# Sheet1.net
KiCad netlist of a schematic drawn in Altium Designer
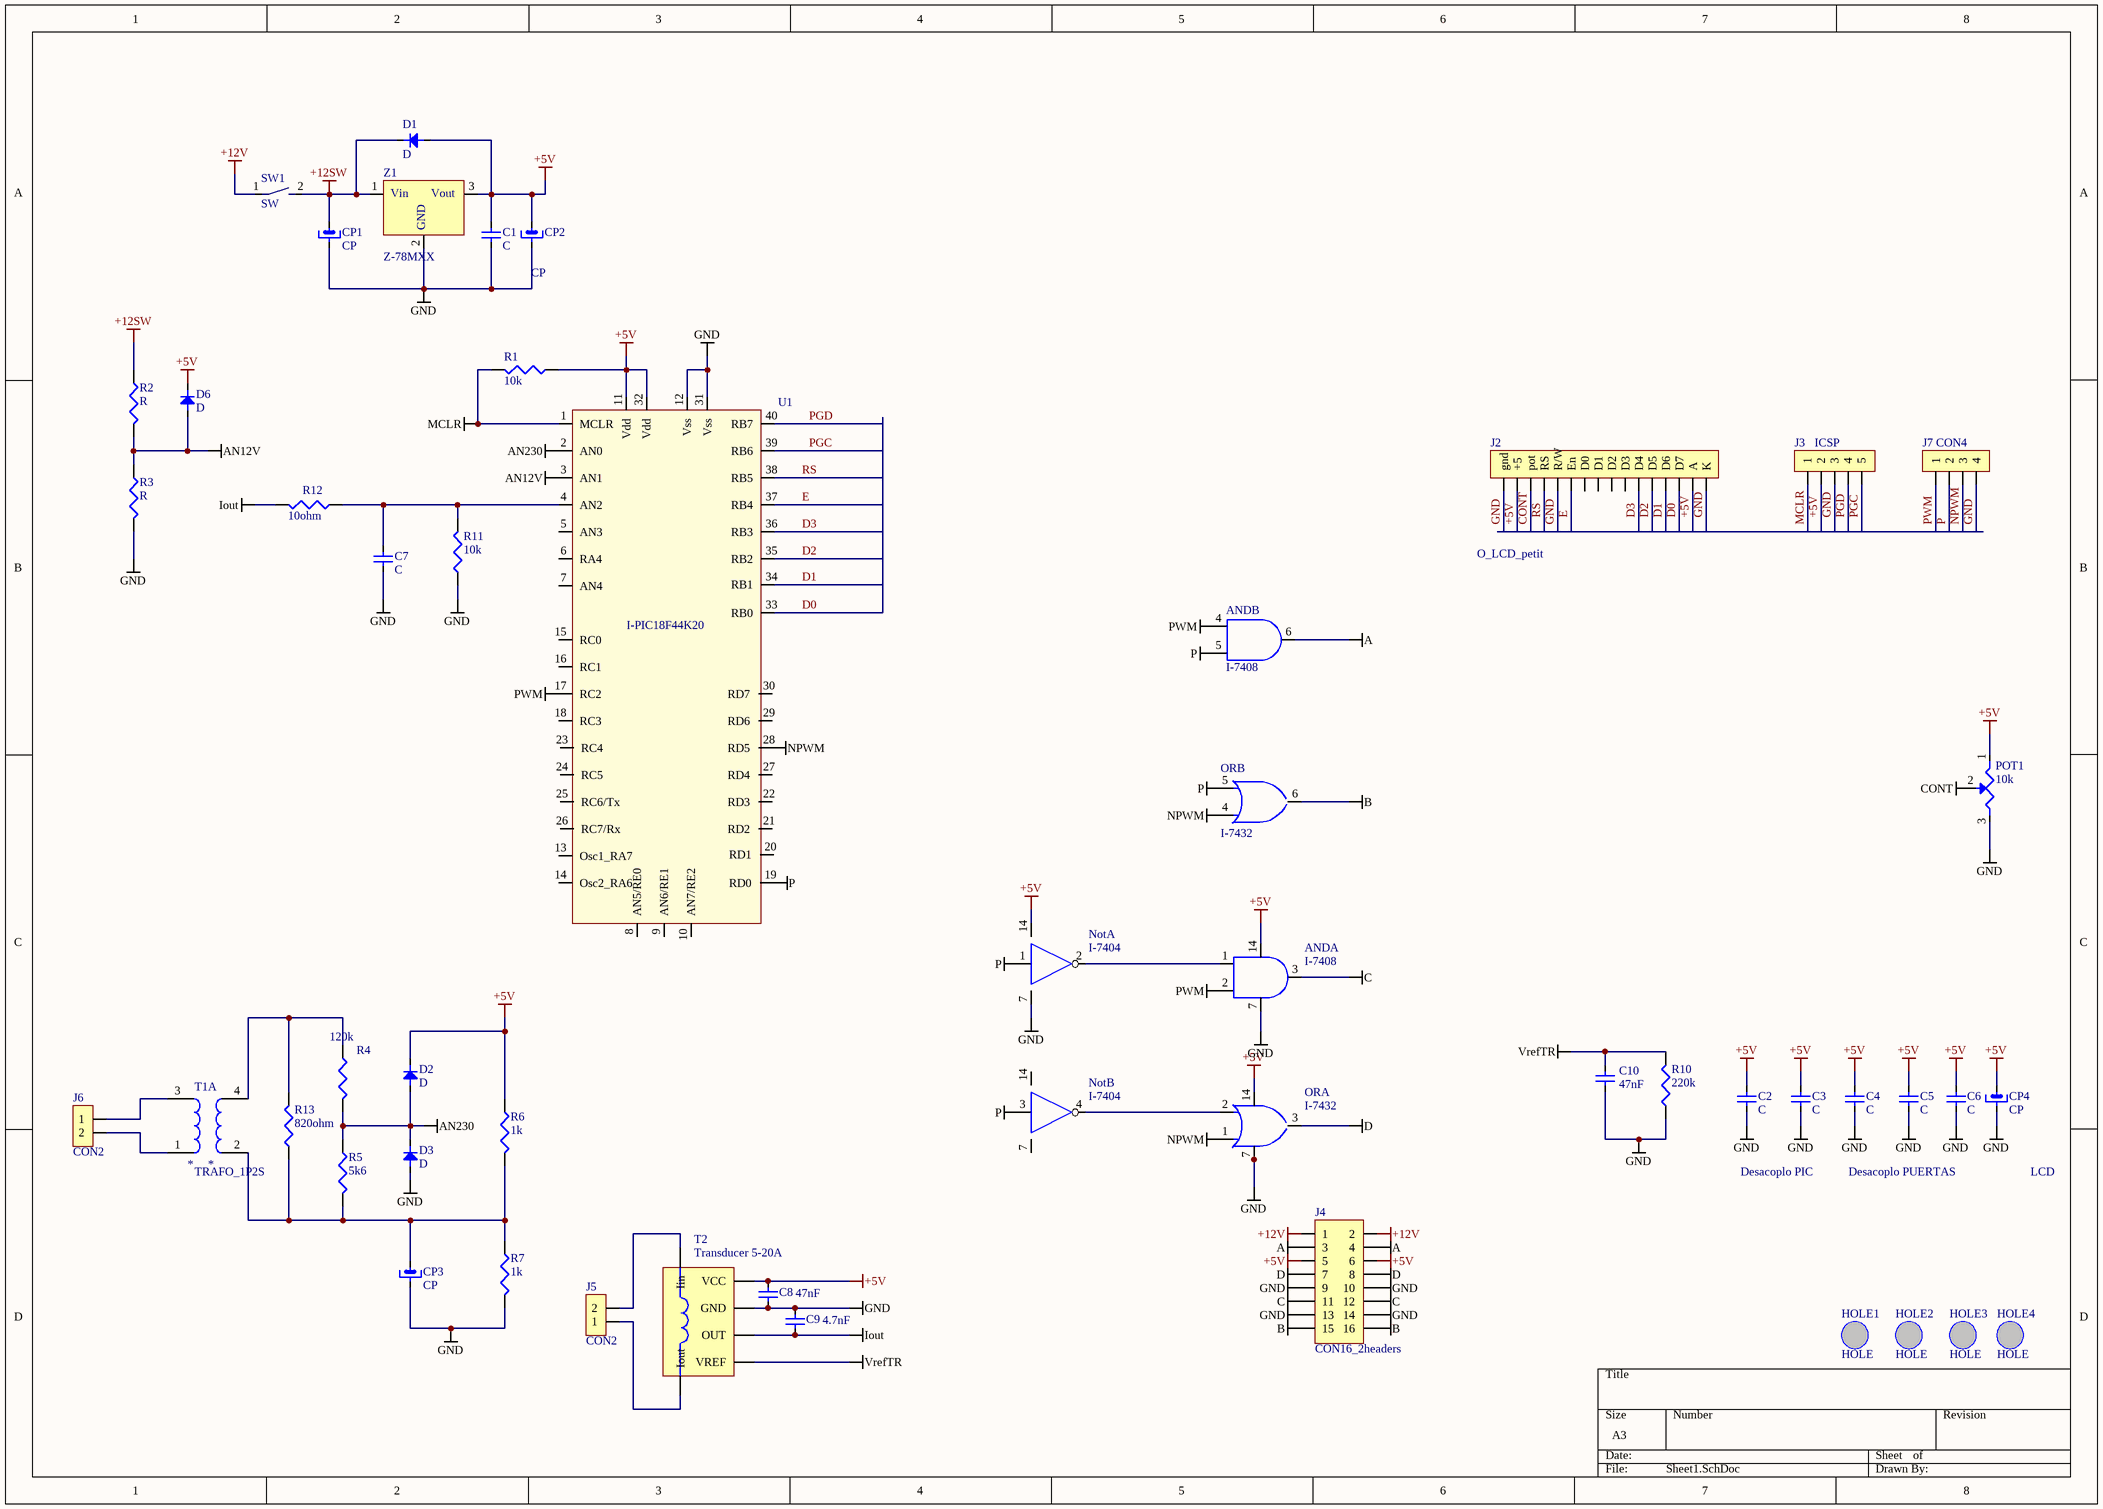
[diagram p0: Sheet1.SchDoc]

(export (version "E")
  (design (tool "Eeschema 10.0.6"))
  (components
    (comp (ref "AND")
      (value "I-7408")
      (footprint "DIP14")
      (description "Cuadruple 2 input Schmitt trigger NAND gate")
      (libsource (lib "Symbols_WOME") (part "I-7408"))
    )
    (comp (ref "C1")
      (value "C")
      (footprint "C2_200mils")
      (description ";C?;C1206;C2_25x7i5;C4_15x5 ;C0805 ;Condensador baja potencia ;2")
      (libsource (lib "Symbols_WOME") (part "C"))
    )
    (comp (ref "C2")
      (value "C")
      (footprint "C2_200mils")
      (description ";C?;C1206;C2_25x7i5;C4_15x5 ;C0805 ;Condensador baja potencia ;2")
      (libsource (lib "Symbols_WOME") (part "C"))
    )
    (comp (ref "C3")
      (value "C")
      (footprint "C2_200mils")
      (description ";C?;C1206;C2_25x7i5;C4_15x5 ;C0805 ;Condensador baja potencia ;2")
      (libsource (lib "Symbols_WOME") (part "C"))
    )
    (comp (ref "C4")
      (value "C")
      (footprint "C2_200mils")
      (description ";C?;C1206;C2_25x7i5;C4_15x5 ;C0805 ;Condensador baja potencia ;2")
      (libsource (lib "Symbols_WOME") (part "C"))
    )
    (comp (ref "C5")
      (value "C")
      (footprint "C2_200mils")
      (description ";C?;C1206;C2_25x7i5;C4_15x5 ;C0805 ;Condensador baja potencia ;2")
      (libsource (lib "Symbols_WOME") (part "C"))
    )
    (comp (ref "C6")
      (value "C")
      (footprint "C2_200mils")
      (description ";C?;C1206;C2_25x7i5;C4_15x5 ;C0805 ;Condensador baja potencia ;2")
      (libsource (lib "Symbols_WOME") (part "C"))
    )
    (comp (ref "C7")
      (value "C")
      (footprint "C2_200mils")
      (description ";C?;C1206;C2_25x7i5;C4_15x5 ;C0805 ;Condensador baja potencia ;2")
      (libsource (lib "Symbols_WOME") (part "C"))
    )
    (comp (ref "C8")
      (value "47nF")
      (footprint "C2_200mils")
      (description ";C?;C1206;C2_25x7i5;C4_15x5 ;C0805 ;Condensador baja potencia ;2")
      (libsource (lib "Symbols_WOME") (part "C"))
    )
    (comp (ref "C9")
      (value "4.7nF")
      (footprint "C2_200mils")
      (description ";C?;C1206;C2_25x7i5;C4_15x5 ;C0805 ;Condensador baja potencia ;2")
      (libsource (lib "Symbols_WOME") (part "C"))
    )
    (comp (ref "C10")
      (value "47nF")
      (footprint "C2_200mils")
      (description ";C?;C1206;C2_25x7i5;C4_15x5 ;C0805 ;Condensador baja potencia ;2")
      (libsource (lib "Symbols_WOME") (part "C"))
    )
    (comp (ref "CP1")
      (value "CP")
      (footprint "CP1_D5i5")
      (description ";CP? ;CP1_D5i5 ;CP2_D10i5 ;CP2_D13 ;CP4_D36 ;Condensador polarizado ;3")
      (libsource (lib "Symbols_WOME") (part "CP"))
    )
    (comp (ref "CP2")
      (value "CP")
      (footprint "CP1_D5i5")
      (description ";CP? ;CP1_D5i5 ;CP2_D10i5 ;CP2_D13 ;CP4_D36 ;Condensador polarizado ;3")
      (libsource (lib "Symbols_WOME") (part "CP"))
    )
    (comp (ref "CP3")
      (value "CP")
      (footprint "CP1_D5i5")
      (description ";CP? ;CP1_D5i5 ;CP2_D10i5 ;CP2_D13 ;CP4_D36 ;Condensador polarizado ;3")
      (libsource (lib "Symbols_WOME") (part "CP"))
    )
    (comp (ref "CP4")
      (value "CP")
      (footprint "CP1_D5i5")
      (description ";CP? ;CP1_D5i5 ;CP2_D10i5 ;CP2_D13 ;CP4_D36 ;Condensador polarizado ;3")
      (libsource (lib "Symbols_WOME") (part "CP"))
    )
    (comp (ref "D1")
      (value "D")
      (footprint "DO35")
      (description ";D? ;SOD80;DO41 ;melf ;minimelf ; Diodo de señal o baja potencia ;8")
      (libsource (lib "Symbols_WOME") (part "D"))
    )
    (comp (ref "D2")
      (value "D")
      (footprint "DO35")
      (description ";D? ;SOD80;DO41 ;melf ;minimelf ; Diodo de señal o baja potencia ;8")
      (libsource (lib "Symbols_WOME") (part "D"))
    )
    (comp (ref "D3")
      (value "D")
      (footprint "DO35")
      (description ";D? ;SOD80;DO41 ;melf ;minimelf ; Diodo de señal o baja potencia ;8")
      (libsource (lib "Symbols_WOME") (part "D"))
    )
    (comp (ref "D6")
      (value "D")
      (footprint "DO35")
      (description ";D? ;SOD80;DO41 ;melf ;minimelf ; Diodo de señal o baja potencia ;8")
      (libsource (lib "Symbols_WOME") (part "D"))
    )
    (comp (ref "HOLE1")
      (value "HOLE")
      (footprint "HOLE3_D6")
      (description ";HOLE? ;HOLE3_D6 ; ; ;Agujero ;20")
      (libsource (lib "Symbols_WOME") (part "HOLE"))
    )
    (comp (ref "HOLE2")
      (value "HOLE")
      (footprint "HOLE3_D6")
      (description ";HOLE? ;HOLE3_D6 ; ; ;Agujero ;20")
      (libsource (lib "Symbols_WOME") (part "HOLE"))
    )
    (comp (ref "HOLE3")
      (value "HOLE")
      (footprint "HOLE3_D6")
      (description ";HOLE? ;HOLE3_D6 ; ; ;Agujero ;20")
      (libsource (lib "Symbols_WOME") (part "HOLE"))
    )
    (comp (ref "HOLE4")
      (value "HOLE")
      (footprint "HOLE3_D6")
      (description ";HOLE? ;HOLE3_D6 ; ; ;Agujero ;20")
      (libsource (lib "Symbols_WOME") (part "HOLE"))
    )
    (comp (ref "J2")
      (value "O_LCD_petit")
      (footprint "O_LCDpetit")
      (libsource (lib "Symbols_WOME") (part "O_LCD_petit"))
    )
    (comp (ref "J3")
      (value "ICSP")
      (footprint "CON5_2I54V")
      (description ";J? ;CON5 ;CON5_2i54VE_JST_B2PVH ;CON5_7I62_STL960-HG-3 ;CON5_2I54V;Conector de 5 pins simples ;17")
      (libsource (lib "Symbols_WOME") (part "CON5"))
    )
    (comp (ref "J4")
      (value "CON16_2headers")
      (footprint "CON16-2headers")
      (description ";J? ;CON5 ;CON5_2i54VE_JST_B2PVH ;CON5_7I62_STL960-HG-3 ;CON5_2I54V;Conector de 5 pins simples ;17")
      (libsource (lib "Symbols_WOME") (part "CON16_2headers"))
    )
    (comp (ref "J5")
      (value "CON2")
      (footprint "CON2_5I08V_CP")
      (libsource (lib "Symbols_WOME") (part "CON2"))
    )
    (comp (ref "J6") (value "CON2") (footprint "CON2_5I08V_CP") (libsource (lib "") (part "CON2_1")))
    (comp (ref "J7") (value "CON4") (footprint "CON4_2I54V") (libsource (lib "Symbols_WOME") (part "CON4")))
    (comp (ref "Not")
      (value "I-7404")
      (footprint "DIP14")
      (description ";U? ;DIP-14 ; ; ; ;6xInversor trigger smith ;18")
      (libsource (lib "Symbols_WOME") (part "I-7404"))
    )
    (comp (ref "OR")
      (value "I-7432")
      (footprint "DIP14")
      (description ";U? ;SOIC14 ; ; ; ; NOR x 4 ;18")
      (libsource (lib "Symbols_WOME") (part "I-7432"))
    )
    (comp (ref "POT1")
      (value "10k")
      (footprint "PT15V")
      (description ";PT? ;PTV1 ;PT15V ;PTH ;PTH1 ;Potenciometro generico ;1")
      (libsource (lib "Symbols_WOME") (part "POT1"))
    )
    (comp (ref "R1")
      (value "10k")
      (footprint "R1/4")
      (description ";R? ;R1206 ;R1/4 ;R1/2 ;R0805 ;Resistencia baja potencia (<=1/2W) ;1")
      (libsource (lib "Symbols_WOME") (part "R"))
    )
    (comp (ref "R2")
      (value "R")
      (footprint "R1/4")
      (description ";R? ;R1206 ;R1/4 ;R1/2 ;R0805 ;Resistencia baja potencia (<=1/2W) ;1")
      (libsource (lib "Symbols_WOME") (part "R"))
    )
    (comp (ref "R3")
      (value "R")
      (footprint "R1/4")
      (description ";R? ;R1206 ;R1/4 ;R1/2 ;R0805 ;Resistencia baja potencia (<=1/2W) ;1")
      (libsource (lib "Symbols_WOME") (part "R"))
    )
    (comp (ref "R4")
      (value "120k")
      (footprint "R1/4")
      (description ";R? ;R1206 ;R1/4 ;R1/2 ;R0805 ;Resistencia baja potencia (<=1/2W) ;1")
      (libsource (lib "Symbols_WOME") (part "R"))
    )
    (comp (ref "R5")
      (value "5k6")
      (footprint "R1/4")
      (description ";R? ;R1206 ;R1/4 ;R1/2 ;R0805 ;Resistencia baja potencia (<=1/2W) ;1")
      (libsource (lib "Symbols_WOME") (part "R"))
    )
    (comp (ref "R6")
      (value "1k")
      (footprint "R1/4")
      (description ";R? ;R1206 ;R1/4 ;R1/2 ;R0805 ;Resistencia baja potencia (<=1/2W) ;1")
      (libsource (lib "Symbols_WOME") (part "R"))
    )
    (comp (ref "R7")
      (value "1k")
      (footprint "R1/4")
      (description ";R? ;R1206 ;R1/4 ;R1/2 ;R0805 ;Resistencia baja potencia (<=1/2W) ;1")
      (libsource (lib "Symbols_WOME") (part "R"))
    )
    (comp (ref "R10")
      (value "220k")
      (footprint "R1/4")
      (description ";R? ;R1206 ;R1/4 ;R1/2 ;R0805 ;Resistencia baja potencia (<=1/2W) ;1")
      (libsource (lib "Symbols_WOME") (part "R"))
    )
    (comp (ref "R11")
      (value "10k")
      (footprint "R1/4")
      (description ";R? ;R1206 ;R1/4 ;R1/2 ;R0805 ;Resistencia baja potencia (<=1/2W) ;1")
      (libsource (lib "Symbols_WOME") (part "R"))
    )
    (comp (ref "R12")
      (value "10ohm")
      (footprint "R1/4")
      (description ";R? ;R1206 ;R1/4 ;R1/2 ;R0805 ;Resistencia baja potencia (<=1/2W) ;1")
      (libsource (lib "Symbols_WOME") (part "R"))
    )
    (comp (ref "R13")
      (value "820ohm")
      (footprint "R1/4")
      (description ";R? ;R1206 ;R1/4 ;R1/2 ;R0805 ;Resistencia baja potencia (<=1/2W) ;1")
      (libsource (lib "Symbols_WOME") (part "R"))
    )
    (comp (ref "SW1")
      (value "SW")
      (footprint "SW1SPDT")
      (description ";SW? ; ; ; ; ;Switch ;")
      (libsource (lib "Symbols_WOME") (part "SW"))
    )
    (comp (ref "T1")
      (value "TRAFO_1P2S")
      (footprint "TR_0.35/1/12")
      (description ";T? ;TR-TOR1P-2S ; ; ; ;Transformador con 2 secundarios \"2part\" ;6")
      (libsource (lib "Symbols_WOME") (part "TRAFO_1P2S"))
    )
    (comp (ref "T2")
      (value "Transducer 5-20A")
      (footprint "HXS 20-NP")
      (libsource (lib "Symbols_WOME") (part "Transducer 5-20A"))
    )
    (comp (ref "U1")
      (value "I-PIC18F44K20")
      (footprint "DIP40")
      (libsource (lib "Symbols_WOME") (part "I-PIC18F44K20"))
    )
    (comp (ref "Z1")
      (value "Z-78MXX")
      (footprint "TO220GDS_pla")
      (description ";Z? ;TO220 ;SOT233 ;TO220H_2COM ; ;Regulador Lineal ;11")
      (libsource (lib "Symbols_WOME") (part "Z-78MXX"))
    )
  )
  (nets
    (net (code "1") (name "+5V") (class "Default")
      (node (ref "AND") (pin "14") (pinfunction "VCC_14") (pintype "passive"))
      (node (ref "C1") (pin "1") (pinfunction "1_1") (pintype "passive"))
      (node (ref "C2") (pin "1") (pinfunction "1_1") (pintype "passive"))
      (node (ref "C3") (pin "1") (pinfunction "1_1") (pintype "passive"))
      (node (ref "C4") (pin "1") (pinfunction "1_1") (pintype "passive"))
      (node (ref "C5") (pin "1") (pinfunction "1_1") (pintype "passive"))
      (node (ref "C6") (pin "1") (pinfunction "1_1") (pintype "passive"))
      (node (ref "C8") (pin "1") (pinfunction "1_1") (pintype "passive"))
      (node (ref "CP2") (pin "1") (pinfunction "1_1") (pintype "passive"))
      (node (ref "CP4") (pin "1") (pinfunction "1_1") (pintype "passive"))
      (node (ref "D1") (pin "1") (pinfunction "1_1") (pintype "passive"))
      (node (ref "D2") (pin "2") (pinfunction "2_2") (pintype "passive"))
      (node (ref "D6") (pin "2") (pinfunction "2_2") (pintype "passive"))
      (node (ref "J2") (pin "15") (pinfunction "A_15") (pintype "passive"))
      (node (ref "J2") (pin "2") (pinfunction "+5_2") (pintype "passive"))
      (node (ref "J3") (pin "2") (pinfunction "2_2") (pintype "passive"))
      (node (ref "J4") (pin "5") (pinfunction "5_5") (pintype "passive"))
      (node (ref "J4") (pin "6") (pinfunction "6_6") (pintype "passive"))
      (node (ref "Not") (pin "14") (pinfunction "VCC_14") (pintype "power_in"))
      (node (ref "OR") (pin "14") (pintype "passive"))
      (node (ref "POT1") (pin "1") (pinfunction "1_1") (pintype "passive"))
      (node (ref "R1") (pin "1") (pinfunction "1_1") (pintype "passive"))
      (node (ref "R6") (pin "1") (pinfunction "1_1") (pintype "passive"))
      (node (ref "T2") (pin "9") (pinfunction "VCC_9") (pintype "passive"))
      (node (ref "U1") (pin "11") (pinfunction "Vdd_11") (pintype "passive"))
      (node (ref "U1") (pin "32") (pinfunction "Vdd_32") (pintype "passive"))
      (node (ref "Z1") (pin "3") (pinfunction "3_3") (pintype "passive"))
    )
    (net (code "2") (name "+12SW") (class "Default")
      (node (ref "CP1") (pin "1") (pinfunction "1_1") (pintype "passive"))
      (node (ref "D1") (pin "2") (pinfunction "2_2") (pintype "passive"))
      (node (ref "R2") (pin "1") (pinfunction "1_1") (pintype "passive"))
      (node (ref "SW1") (pin "2") (pinfunction "2_2") (pintype "passive"))
      (node (ref "Z1") (pin "1") (pinfunction "1_1") (pintype "passive"))
    )
    (net (code "3") (name "+12V") (class "Default")
      (node (ref "J4") (pin "1") (pinfunction "1_1") (pintype "passive"))
      (node (ref "J4") (pin "2") (pinfunction "2_2") (pintype "passive"))
      (node (ref "SW1") (pin "1") (pinfunction "1_1") (pintype "passive"))
    )
    (net (code "4") (name "/D0") (class "Default")
      (node (ref "J2") (pin "14") (pinfunction "D7_14") (pintype "passive"))
      (node (ref "U1") (pin "33") (pinfunction "RB0_33") (pintype "passive"))
    )
    (net (code "5") (name "/D1") (class "Default")
      (node (ref "J2") (pin "13") (pinfunction "D6_13") (pintype "passive"))
      (node (ref "U1") (pin "34") (pinfunction "RB1_34") (pintype "passive"))
    )
    (net (code "6") (name "/D2") (class "Default")
      (node (ref "J2") (pin "12") (pinfunction "D5_12") (pintype "passive"))
      (node (ref "U1") (pin "35") (pinfunction "RB2_35") (pintype "passive"))
    )
    (net (code "7") (name "/D3") (class "Default")
      (node (ref "J2") (pin "11") (pinfunction "D4_11") (pintype "passive"))
      (node (ref "U1") (pin "36") (pinfunction "RB3_36") (pintype "passive"))
    )
    (net (code "8") (name "/E") (class "Default")
      (node (ref "J2") (pin "6") (pinfunction "En_6") (pintype "passive"))
      (node (ref "U1") (pin "37") (pinfunction "RB4_37") (pintype "passive"))
    )
    (net (code "9") (name "/PGC") (class "Default")
      (node (ref "J3") (pin "5") (pinfunction "5_5") (pintype "passive"))
      (node (ref "U1") (pin "39") (pinfunction "RB6_39") (pintype "passive"))
    )
    (net (code "10") (name "/PGD") (class "Default")
      (node (ref "J3") (pin "4") (pinfunction "4_4") (pintype "passive"))
      (node (ref "U1") (pin "40") (pinfunction "RB7_40") (pintype "passive"))
    )
    (net (code "11") (name "/RS") (class "Default")
      (node (ref "J2") (pin "4") (pinfunction "RS_4") (pintype "passive"))
      (node (ref "U1") (pin "38") (pinfunction "RB5_38") (pintype "passive"))
    )
    (net (code "12") (name "A") (class "Default")
      (node (ref "AND") (pin "6") (pinfunction "BO_6") (pintype "passive"))
      (node (ref "J4") (pin "3") (pinfunction "3_3") (pintype "passive"))
      (node (ref "J4") (pin "4") (pinfunction "4_4") (pintype "passive"))
    )
    (net (code "13") (name "AN12V") (class "Default")
      (node (ref "D6") (pin "1") (pinfunction "1_1") (pintype "passive"))
      (node (ref "R2") (pin "2") (pinfunction "2_2") (pintype "passive"))
      (node (ref "R3") (pin "1") (pinfunction "1_1") (pintype "passive"))
      (node (ref "U1") (pin "3") (pinfunction "AN1_3") (pintype "passive"))
    )
    (net (code "14") (name "AN230") (class "Default")
      (node (ref "D2") (pin "1") (pinfunction "1_1") (pintype "passive"))
      (node (ref "D3") (pin "2") (pinfunction "2_2") (pintype "passive"))
      (node (ref "R4") (pin "2") (pinfunction "2_2") (pintype "passive"))
      (node (ref "R5") (pin "1") (pinfunction "1_1") (pintype "passive"))
      (node (ref "U1") (pin "2") (pinfunction "AN0_2") (pintype "passive"))
    )
    (net (code "15") (name "B") (class "Default")
      (node (ref "J4") (pin "15") (pinfunction "15_15") (pintype "passive"))
      (node (ref "J4") (pin "16") (pinfunction "16_16") (pintype "passive"))
      (node (ref "OR") (pin "6") (pintype "passive"))
    )
    (net (code "16") (name "C") (class "Default")
      (node (ref "AND") (pin "3") (pinfunction "AO_3") (pintype "passive"))
      (node (ref "J4") (pin "11") (pinfunction "11_11") (pintype "passive"))
      (node (ref "J4") (pin "12") (pinfunction "12_12") (pintype "passive"))
    )
    (net (code "17") (name "CONT") (class "Default")
      (node (ref "J2") (pin "3") (pinfunction "pot_3") (pintype "passive"))
      (node (ref "POT1") (pin "2") (pinfunction "2_2") (pintype "passive"))
    )
    (net (code "18") (name "D") (class "Default")
      (node (ref "J4") (pin "7") (pinfunction "7_7") (pintype "passive"))
      (node (ref "J4") (pin "8") (pinfunction "8_8") (pintype "passive"))
      (node (ref "OR") (pin "3") (pintype "passive"))
    )
    (net (code "19") (name "GND") (class "Default")
      (node (ref "AND") (pin "7") (pinfunction "GND_7") (pintype "passive"))
      (node (ref "C1") (pin "2") (pinfunction "2_2") (pintype "passive"))
      (node (ref "C10") (pin "2") (pinfunction "2_2") (pintype "passive"))
      (node (ref "C2") (pin "2") (pinfunction "2_2") (pintype "passive"))
      (node (ref "C3") (pin "2") (pinfunction "2_2") (pintype "passive"))
      (node (ref "C4") (pin "2") (pinfunction "2_2") (pintype "passive"))
      (node (ref "C5") (pin "2") (pinfunction "2_2") (pintype "passive"))
      (node (ref "C6") (pin "2") (pinfunction "2_2") (pintype "passive"))
      (node (ref "C7") (pin "2") (pinfunction "2_2") (pintype "passive"))
      (node (ref "C8") (pin "2") (pinfunction "2_2") (pintype "passive"))
      (node (ref "C9") (pin "1") (pinfunction "1_1") (pintype "passive"))
      (node (ref "CP1") (pin "2") (pinfunction "2_2") (pintype "passive"))
      (node (ref "CP2") (pin "2") (pinfunction "2_2") (pintype "passive"))
      (node (ref "CP3") (pin "2") (pinfunction "2_2") (pintype "passive"))
      (node (ref "CP4") (pin "2") (pinfunction "2_2") (pintype "passive"))
      (node (ref "D3") (pin "1") (pinfunction "1_1") (pintype "passive"))
      (node (ref "J2") (pin "1") (pinfunction "gnd_1") (pintype "passive"))
      (node (ref "J2") (pin "16") (pinfunction "K_16") (pintype "passive"))
      (node (ref "J2") (pin "5") (pinfunction "R/W_5") (pintype "passive"))
      (node (ref "J3") (pin "3") (pinfunction "3_3") (pintype "passive"))
      (node (ref "J4") (pin "10") (pinfunction "10_10") (pintype "passive"))
      (node (ref "J4") (pin "13") (pinfunction "13_13") (pintype "passive"))
      (node (ref "J4") (pin "14") (pinfunction "14_14") (pintype "passive"))
      (node (ref "J4") (pin "9") (pinfunction "9_9") (pintype "passive"))
      (node (ref "J7") (pin "4") (pinfunction "4_4") (pintype "passive"))
      (node (ref "Not") (pin "7") (pinfunction "GND_7") (pintype "power_in"))
      (node (ref "OR") (pin "7") (pintype "passive"))
      (node (ref "POT1") (pin "3") (pinfunction "3_3") (pintype "passive"))
      (node (ref "R10") (pin "1") (pinfunction "1_1") (pintype "passive"))
      (node (ref "R11") (pin "1") (pinfunction "1_1") (pintype "passive"))
      (node (ref "R3") (pin "2") (pinfunction "2_2") (pintype "passive"))
      (node (ref "R7") (pin "2") (pinfunction "2_2") (pintype "passive"))
      (node (ref "T2") (pin "10") (pinfunction "GND_10") (pintype "passive"))
      (node (ref "U1") (pin "12") (pinfunction "Vss_12") (pintype "passive"))
      (node (ref "U1") (pin "31") (pinfunction "Vss_31") (pintype "passive"))
      (node (ref "Z1") (pin "2") (pinfunction "2_2") (pintype "passive"))
    )
    (net (code "20") (name "Iout") (class "Default")
      (node (ref "C9") (pin "2") (pinfunction "2_2") (pintype "passive"))
      (node (ref "R12") (pin "2") (pinfunction "2_2") (pintype "passive"))
      (node (ref "T2") (pin "11") (pinfunction "OUT_11") (pintype "passive"))
    )
    (net (code "21") (name "MCLR") (class "Default")
      (node (ref "J3") (pin "1") (pinfunction "1_1") (pintype "passive"))
      (node (ref "R1") (pin "2") (pinfunction "2_2") (pintype "passive"))
      (node (ref "U1") (pin "1") (pinfunction "MCLR_1") (pintype "passive"))
    )
    (net (code "22") (name "NPWM") (class "Default")
      (node (ref "J7") (pin "3") (pinfunction "3_3") (pintype "passive"))
      (node (ref "OR") (pin "1") (pintype "passive"))
      (node (ref "OR") (pin "4") (pintype "passive"))
      (node (ref "U1") (pin "28") (pinfunction "RD5_28") (pintype "passive"))
    )
    (net (code "23") (name "Net-(ANDA-A1)") (class "Default")
      (node (ref "AND") (pin "1") (pinfunction "A1_1") (pintype "passive"))
      (node (ref "Not") (pin "2") (pintype "passive"))
    )
    (net (code "24") (name "Net-(CP3-Pad1)") (class "Default")
      (node (ref "CP3") (pin "1") (pinfunction "1_1") (pintype "passive"))
      (node (ref "R13") (pin "1") (pinfunction "1_1") (pintype "passive"))
      (node (ref "R5") (pin "2") (pinfunction "2_2") (pintype "passive"))
      (node (ref "R6") (pin "2") (pinfunction "2_2") (pintype "passive"))
      (node (ref "R7") (pin "1") (pinfunction "1_1") (pintype "passive"))
      (node (ref "T1") (pin "2") (pinfunction "2_2") (pintype "passive"))
    )
    (net (code "25") (name "Net-(J6-Pad1)") (class "Default")
      (node (ref "J6") (pin "1") (pinfunction "1_1") (pintype "passive"))
      (node (ref "T1") (pin "3") (pinfunction "3_3") (pintype "passive"))
    )
    (net (code "26") (name "Net-(J6-Pad2)") (class "Default")
      (node (ref "J6") (pin "2") (pinfunction "2_2") (pintype "passive"))
      (node (ref "T1") (pin "1") (pinfunction "1_1") (pintype "passive"))
    )
    (net (code "27") (name "Net-(Not-Pad4)") (class "Default")
      (node (ref "Not") (pin "4") (pintype "passive"))
      (node (ref "OR") (pin "2") (pintype "passive"))
    )
    (net (code "28") (name "Net-(R13-Pad2)") (class "Default")
      (node (ref "R13") (pin "2") (pinfunction "2_2") (pintype "passive"))
      (node (ref "R4") (pin "1") (pinfunction "1_1") (pintype "passive"))
      (node (ref "T1") (pin "4") (pinfunction "4_4") (pintype "passive"))
    )
    (net (code "29") (name "Net-(T2-Iin)") (class "Default")
      (node (ref "J5") (pin "2") (pinfunction "2_2") (pintype "passive"))
      (node (ref "T2") (pin "1") (pinfunction "Iin_1") (pintype "passive"))
    )
    (net (code "30") (name "Net-(T2-Iout)") (class "Default")
      (node (ref "J5") (pin "1") (pinfunction "1_1") (pintype "passive"))
      (node (ref "T2") (pin "8") (pinfunction "Iout_8") (pintype "passive"))
    )
    (net (code "31") (name "Net-(U1-AN2)") (class "Default")
      (node (ref "C7") (pin "1") (pinfunction "1_1") (pintype "passive"))
      (node (ref "R11") (pin "2") (pinfunction "2_2") (pintype "passive"))
      (node (ref "R12") (pin "1") (pinfunction "1_1") (pintype "passive"))
      (node (ref "U1") (pin "4") (pinfunction "AN2_4") (pintype "passive"))
    )
    (net (code "32") (name "P") (class "Default")
      (node (ref "AND") (pin "5") (pinfunction "B2_5") (pintype "passive"))
      (node (ref "J7") (pin "2") (pinfunction "2_2") (pintype "passive"))
      (node (ref "Not") (pin "1") (pintype "passive"))
      (node (ref "Not") (pin "3") (pintype "passive"))
      (node (ref "OR") (pin "5") (pintype "passive"))
      (node (ref "U1") (pin "19") (pinfunction "RD0_19") (pintype "passive"))
    )
    (net (code "33") (name "PWM") (class "Default")
      (node (ref "AND") (pin "2") (pinfunction "A2_2") (pintype "passive"))
      (node (ref "AND") (pin "4") (pinfunction "B1_4") (pintype "passive"))
      (node (ref "J7") (pin "1") (pinfunction "1_1") (pintype "passive"))
      (node (ref "U1") (pin "17") (pinfunction "RC2_17") (pintype "passive"))
    )
    (net (code "34") (name "VrefTR") (class "Default")
      (node (ref "C10") (pin "1") (pinfunction "1_1") (pintype "passive"))
      (node (ref "R10") (pin "2") (pinfunction "2_2") (pintype "passive"))
      (node (ref "T2") (pin "12") (pinfunction "VREF_12") (pintype "passive"))
    )
    (net (code "35") (name "unconnected-(J2-D0-Pad7)") (class "Default")
      (node (ref "J2") (pin "7") (pinfunction "D0_7") (pintype "passive"))
    )
    (net (code "36") (name "unconnected-(J2-D1-Pad8)") (class "Default")
      (node (ref "J2") (pin "8") (pinfunction "D1_8") (pintype "passive"))
    )
    (net (code "37") (name "unconnected-(J2-D2-Pad9)") (class "Default")
      (node (ref "J2") (pin "9") (pinfunction "D2_9") (pintype "passive"))
    )
    (net (code "38") (name "unconnected-(J2-D3-Pad10)") (class "Default")
      (node (ref "J2") (pin "10") (pinfunction "D3_10") (pintype "passive"))
    )
    (net (code "39") (name "unconnected-(U1-AN3-Pad5)") (class "Default")
      (node (ref "U1") (pin "5") (pinfunction "AN3_5") (pintype "passive"))
    )
    (net (code "40") (name "unconnected-(U1-AN4-Pad7)") (class "Default")
      (node (ref "U1") (pin "7") (pinfunction "AN4_7") (pintype "passive"))
    )
    (net (code "41") (name "unconnected-(U1-AN5{slash}RE0-Pad8)") (class "Default")
      (node (ref "U1") (pin "8") (pinfunction "AN5/RE0_8") (pintype "passive"))
    )
    (net (code "42") (name "unconnected-(U1-AN6{slash}RE1-Pad9)") (class "Default")
      (node (ref "U1") (pin "9") (pinfunction "AN6/RE1_9") (pintype "passive"))
    )
    (net (code "43") (name "unconnected-(U1-AN7{slash}RE2-Pad10)") (class "Default")
      (node (ref "U1") (pin "10") (pinfunction "AN7/RE2_10") (pintype "passive"))
    )
    (net (code "44") (name "unconnected-(U1-Osc1_RA7-Pad13)") (class "Default")
      (node (ref "U1") (pin "13") (pinfunction "Osc1_RA7_13") (pintype "passive"))
    )
    (net (code "45") (name "unconnected-(U1-Osc2_RA6-Pad14)") (class "Default")
      (node (ref "U1") (pin "14") (pinfunction "Osc2_RA6_14") (pintype "passive"))
    )
    (net (code "46") (name "unconnected-(U1-RA4-Pad6)") (class "Default")
      (node (ref "U1") (pin "6") (pinfunction "RA4_6") (pintype "passive"))
    )
    (net (code "47") (name "unconnected-(U1-RC0-Pad15)") (class "Default")
      (node (ref "U1") (pin "15") (pinfunction "RC0_15") (pintype "passive"))
    )
    (net (code "48") (name "unconnected-(U1-RC1-Pad16)") (class "Default")
      (node (ref "U1") (pin "16") (pinfunction "RC1_16") (pintype "passive"))
    )
    (net (code "49") (name "unconnected-(U1-RC3-Pad18)") (class "Default")
      (node (ref "U1") (pin "18") (pinfunction "RC3_18") (pintype "passive"))
    )
    (net (code "50") (name "unconnected-(U1-RC4-Pad23)") (class "Default")
      (node (ref "U1") (pin "23") (pinfunction "RC4_23") (pintype "passive"))
    )
    (net (code "51") (name "unconnected-(U1-RC5-Pad24)") (class "Default")
      (node (ref "U1") (pin "24") (pinfunction "RC5_24") (pintype "passive"))
    )
    (net (code "52") (name "unconnected-(U1-RC6{slash}Tx-Pad25)") (class "Default")
      (node (ref "U1") (pin "25") (pinfunction "RC6/Tx_25") (pintype "passive"))
    )
    (net (code "53") (name "unconnected-(U1-RC7{slash}Rx-Pad26)") (class "Default")
      (node (ref "U1") (pin "26") (pinfunction "RC7/Rx_26") (pintype "passive"))
    )
    (net (code "54") (name "unconnected-(U1-RD1-Pad20)") (class "Default")
      (node (ref "U1") (pin "20") (pinfunction "RD1_20") (pintype "passive"))
    )
    (net (code "55") (name "unconnected-(U1-RD2-Pad21)") (class "Default")
      (node (ref "U1") (pin "21") (pinfunction "RD2_21") (pintype "passive"))
    )
    (net (code "56") (name "unconnected-(U1-RD3-Pad22)") (class "Default")
      (node (ref "U1") (pin "22") (pinfunction "RD3_22") (pintype "passive"))
    )
    (net (code "57") (name "unconnected-(U1-RD4-Pad27)") (class "Default")
      (node (ref "U1") (pin "27") (pinfunction "RD4_27") (pintype "passive"))
    )
    (net (code "58") (name "unconnected-(U1-RD6-Pad29)") (class "Default")
      (node (ref "U1") (pin "29") (pinfunction "RD6_29") (pintype "passive"))
    )
    (net (code "59") (name "unconnected-(U1-RD7-Pad30)") (class "Default")
      (node (ref "U1") (pin "30") (pinfunction "RD7_30") (pintype "passive"))
    )
  )
)
